# sailpi-hat.net
KiCad netlist of a schematic drawn in EAGLE
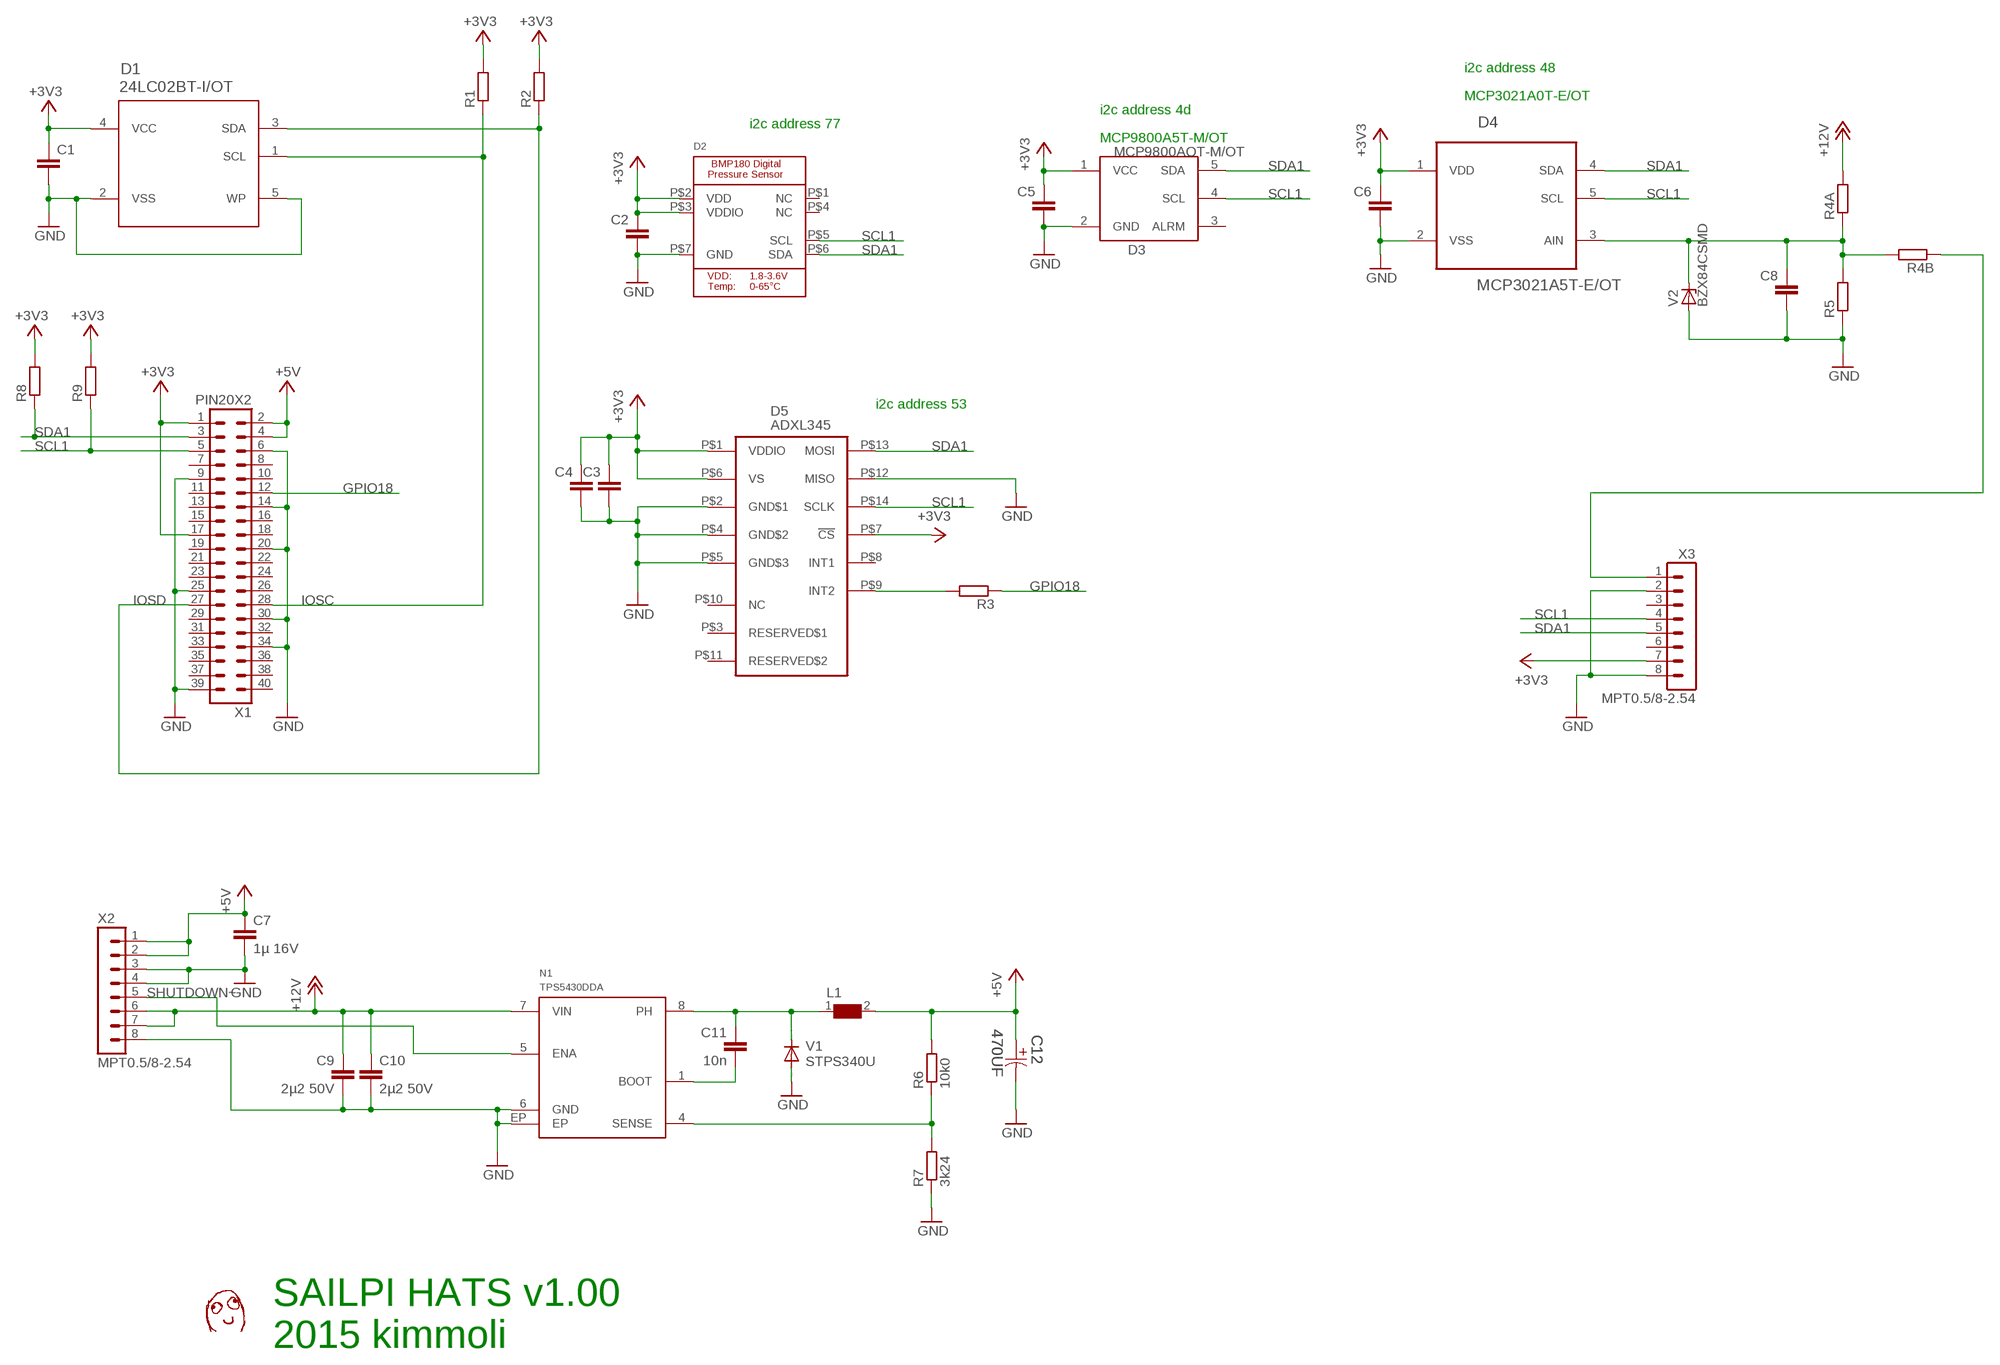
[diagram p0: schematic, sheet 1]

(export (version "E")
  (design (tool "Eeschema 10.0.6"))
  (components
    (comp (ref "C1")
      (value "CAP0603")
      (footprint "eagle-import:C0603")
      (libsource (lib "eagle-import") (part "omat_ic_2_CAP0603"))
    )
    (comp (ref "C2")
      (value "CAP0603")
      (footprint "eagle-import:C0603")
      (libsource (lib "eagle-import") (part "omat_ic_2_CAP0603"))
    )
    (comp (ref "C3")
      (value "CAP0603")
      (footprint "eagle-import:C0603")
      (libsource (lib "eagle-import") (part "omat_ic_2_CAP0603"))
    )
    (comp (ref "C4")
      (value "CAP0603")
      (footprint "eagle-import:C0603")
      (libsource (lib "eagle-import") (part "omat_ic_2_CAP0603"))
    )
    (comp (ref "C5")
      (value "CAP0603")
      (footprint "eagle-import:C0603")
      (libsource (lib "eagle-import") (part "omat_ic_2_CAP0603"))
    )
    (comp (ref "C6")
      (value "CAP0603")
      (footprint "eagle-import:C0603")
      (libsource (lib "eagle-import") (part "omat_ic_2_CAP0603"))
    )
    (comp (ref "C7")
      (value "1µ 16V")
      (footprint "eagle-import:C0805")
      (libsource (lib "eagle-import") (part "CAP0805"))
    )
    (comp (ref "C8")
      (value "CAP0603")
      (footprint "eagle-import:C0603")
      (libsource (lib "eagle-import") (part "omat_ic_2_CAP0603"))
    )
    (comp (ref "C9")
      (value "2µ2 50V")
      (footprint "eagle-import:C0805")
      (libsource (lib "eagle-import") (part "CAP0805"))
    )
    (comp (ref "C10")
      (value "2µ2 50V")
      (footprint "eagle-import:C0805")
      (libsource (lib "eagle-import") (part "CAP0805"))
    )
    (comp (ref "C11")
      (value "10n")
      (footprint "eagle-import:C0805")
      (libsource (lib "eagle-import") (part "CAP0805"))
    )
    (comp (ref "C12")
      (value "470UF")
      (footprint "eagle-import:CAPAE1350X1400N")
      (fields (field (name "MPN") "EEVFK1V471Q") (field (name "TOLERANCE") "±20 %"))
      (libsource (lib "eagle-import") (part "EEV--CASE-H13FK1V471Q"))
    )
    (comp (ref "D1")
      (value "24LC02BT-I/OT")
      (footprint "eagle-import:SOT95P280X145-5N")
      (libsource (lib "eagle-import") (part "24LC02BT-I/OT"))
    )
    (comp (ref "D2")
      (value "BMP180EXT")
      (footprint "eagle-import:BMP180_EXTENDED")
      (libsource (lib "eagle-import") (part "BMP180EXT"))
    )
    (comp (ref "D3")
      (value "MCP9800AOT-M/OT")
      (footprint "eagle-import:SOT23-5")
      (libsource (lib "eagle-import") (part "MCP9800AOT-M/OT"))
    )
    (comp (ref "D4")
      (value "MCP3021A5T-E/OT")
      (footprint "eagle-import:SOT95P270X145-5N")
      (libsource (lib "eagle-import") (part "MCP3021A5T-E/OT"))
    )
    (comp (ref "D5")
      (value "ADXL345")
      (footprint "eagle-import:LGA14")
      (libsource (lib "eagle-import") (part "ADXL345"))
    )
    (comp (ref "L1")
      (value "WE-PD-7447709220_1260/1245/1280/1210")
      (footprint "eagle-import:WE-PD_1260_1245_1280_1210")
      (fields (field (name "MPN") "7447709220"))
      (libsource (lib "eagle-import") (part "WE-PD_1260/1245/1280/1210-7447709220"))
    )
    (comp (ref "N1")
      (value "TPS5430DDA")
      (footprint "eagle-import:SOIC8-N-EP")
      (libsource (lib "eagle-import") (part "TPS5430DDA"))
    )
    (comp (ref "R1")
      (value "RES0603")
      (footprint "eagle-import:R0603")
      (libsource (lib "eagle-import") (part "omat_ic_2_RES0603"))
    )
    (comp (ref "R2")
      (value "RES0603")
      (footprint "eagle-import:R0603")
      (libsource (lib "eagle-import") (part "omat_ic_2_RES0603"))
    )
    (comp (ref "R3")
      (value "RES0603")
      (footprint "eagle-import:R0603")
      (libsource (lib "eagle-import") (part "omat_ic_2_RES0603"))
    )
    (comp (ref "R4A")
      (value "RES0603")
      (footprint "eagle-import:R0603")
      (libsource (lib "eagle-import") (part "omat_ic_2_RES0603"))
    )
    (comp (ref "R4B")
      (value "RES0603")
      (footprint "eagle-import:R0603")
      (libsource (lib "eagle-import") (part "omat_ic_2_RES0603"))
    )
    (comp (ref "R5")
      (value "RES0603")
      (footprint "eagle-import:R0603")
      (libsource (lib "eagle-import") (part "omat_ic_2_RES0603"))
    )
    (comp (ref "R6")
      (value "10k0")
      (footprint "eagle-import:R0603")
      (libsource (lib "eagle-import") (part "RES0603"))
    )
    (comp (ref "R7")
      (value "3k24")
      (footprint "eagle-import:R0603")
      (libsource (lib "eagle-import") (part "RES0603"))
    )
    (comp (ref "R8")
      (value "RES0603")
      (footprint "eagle-import:R0603")
      (libsource (lib "eagle-import") (part "omat_ic_2_RES0603"))
    )
    (comp (ref "R9")
      (value "RES0603")
      (footprint "eagle-import:R0603")
      (libsource (lib "eagle-import") (part "omat_ic_2_RES0603"))
    )
    (comp (ref "U$2")
      (value "DAFUG")
      (footprint "eagle-import:DAFUG")
      (libsource (lib "eagle-import") (part "DAFUG"))
    )
    (comp (ref "V1")
      (value "STPS340U")
      (footprint "eagle-import:SMB")
      (libsource (lib "eagle-import") (part "DIODE-SMB"))
    )
    (comp (ref "V2")
      (value "BZX84CSMD")
      (footprint "eagle-import:TO236")
      (libsource (lib "eagle-import") (part "BZX84CSMD"))
    )
    (comp (ref "X1")
      (value "PIN20X2")
      (footprint "eagle-import:PIN_20X2")
      (libsource (lib "eagle-import") (part "PIN20X2"))
    )
    (comp (ref "X2")
      (value "MPT0.5/8-2.54")
      (footprint "eagle-import:MPT0.5_8-2.54")
      (libsource (lib "eagle-import") (part "MPT0.5/8-2.54"))
    )
    (comp (ref "X3")
      (value "MPT0.5/8-2.54")
      (footprint "eagle-import:MPT0.5_8-2.54")
      (libsource (lib "eagle-import") (part "MPT0.5/8-2.54"))
    )
  )
  (nets
    (net (code "1") (name "+3V3") (class "Default")
      (node (ref "C1") (pin "1") (pinfunction "1_1") (pintype "passive"))
      (node (ref "C2") (pin "1") (pinfunction "1_1") (pintype "passive"))
      (node (ref "C3") (pin "1") (pinfunction "1_1") (pintype "passive"))
      (node (ref "C4") (pin "1") (pinfunction "1_1") (pintype "passive"))
      (node (ref "C5") (pin "1") (pinfunction "1_1") (pintype "passive"))
      (node (ref "C6") (pin "1") (pinfunction "1_1") (pintype "passive"))
      (node (ref "D1") (pin "4") (pinfunction "VCC_4") (pintype "power_in"))
      (node (ref "D2") (pin "P$2") (pinfunction "VDD_P$2") (pintype "power_in"))
      (node (ref "D2") (pin "P$3") (pinfunction "VDDIO_P$3") (pintype "power_in"))
      (node (ref "D3") (pin "1") (pinfunction "VCC_1") (pintype "bidirectional"))
      (node (ref "D4") (pin "1") (pinfunction "VDD_1") (pintype "power_in"))
      (node (ref "D5") (pin "P$1") (pinfunction "VDDIO_P$1") (pintype "power_in"))
      (node (ref "D5") (pin "P$6") (pinfunction "VS_P$6") (pintype "power_in"))
      (node (ref "D5") (pin "P$7") (pinfunction "~{CS}_P$7") (pintype "input"))
      (node (ref "R1") (pin "2") (pinfunction "2_2") (pintype "passive"))
      (node (ref "R2") (pin "2") (pinfunction "2_2") (pintype "passive"))
      (node (ref "R8") (pin "2") (pinfunction "2_2") (pintype "passive"))
      (node (ref "R9") (pin "2") (pinfunction "2_2") (pintype "passive"))
      (node (ref "X1") (pin "1") (pinfunction "1_1") (pintype "passive"))
      (node (ref "X1") (pin "17") (pinfunction "17_17") (pintype "passive"))
      (node (ref "X3") (pin "7") (pinfunction "7_7") (pintype "passive"))
    )
    (net (code "2") (name "+5V") (class "Default")
      (node (ref "C12") (pin "1") (pinfunction "1_1") (pintype "passive"))
      (node (ref "C7") (pin "1") (pinfunction "1_1") (pintype "passive"))
      (node (ref "L1") (pin "2") (pinfunction "2_2") (pintype "passive"))
      (node (ref "R6") (pin "2") (pinfunction "2_2") (pintype "passive"))
      (node (ref "X1") (pin "2") (pinfunction "2_2") (pintype "passive"))
      (node (ref "X1") (pin "4") (pinfunction "4_4") (pintype "passive"))
      (node (ref "X2") (pin "1") (pinfunction "1_1") (pintype "passive"))
      (node (ref "X2") (pin "2") (pinfunction "2_2") (pintype "passive"))
    )
    (net (code "3") (name "+12V") (class "Default")
      (node (ref "C10") (pin "1") (pinfunction "1_1") (pintype "passive"))
      (node (ref "C9") (pin "1") (pinfunction "1_1") (pintype "passive"))
      (node (ref "N1") (pin "7") (pinfunction "VIN_7") (pintype "bidirectional"))
      (node (ref "R4A") (pin "2") (pinfunction "2_2") (pintype "passive"))
      (node (ref "X2") (pin "6") (pinfunction "6_6") (pintype "passive"))
      (node (ref "X2") (pin "7") (pinfunction "7_7") (pintype "passive"))
    )
    (net (code "4") (name "/GPIO18") (class "Default")
      (node (ref "R3") (pin "1") (pinfunction "1_1") (pintype "passive"))
      (node (ref "X1") (pin "12") (pinfunction "12_12") (pintype "passive"))
    )
    (net (code "5") (name "/IOSC") (class "Default")
      (node (ref "D1") (pin "1") (pinfunction "SCL_1") (pintype "input"))
      (node (ref "R1") (pin "1") (pinfunction "1_1") (pintype "passive"))
      (node (ref "X1") (pin "28") (pinfunction "28_28") (pintype "passive"))
    )
    (net (code "6") (name "/IOSD") (class "Default")
      (node (ref "D1") (pin "3") (pinfunction "SDA_3") (pintype "bidirectional"))
      (node (ref "R2") (pin "1") (pinfunction "1_1") (pintype "passive"))
      (node (ref "X1") (pin "27") (pinfunction "27_27") (pintype "passive"))
    )
    (net (code "7") (name "/SCL1") (class "Default")
      (node (ref "D2") (pin "P$5") (pinfunction "SCL_P$5") (pintype "bidirectional"))
      (node (ref "D3") (pin "4") (pinfunction "SCL_4") (pintype "bidirectional"))
      (node (ref "D4") (pin "5") (pinfunction "SCL_5") (pintype "input"))
      (node (ref "D5") (pin "P$14") (pinfunction "SCLK_P$14") (pintype "input"))
      (node (ref "R9") (pin "1") (pinfunction "1_1") (pintype "passive"))
      (node (ref "X1") (pin "5") (pinfunction "5_5") (pintype "passive"))
      (node (ref "X3") (pin "4") (pinfunction "4_4") (pintype "passive"))
    )
    (net (code "8") (name "/SDA1") (class "Default")
      (node (ref "D2") (pin "P$6") (pinfunction "SDA_P$6") (pintype "bidirectional"))
      (node (ref "D3") (pin "5") (pinfunction "SDA_5") (pintype "bidirectional"))
      (node (ref "D4") (pin "4") (pinfunction "SDA_4") (pintype "bidirectional"))
      (node (ref "D5") (pin "P$13") (pinfunction "MOSI_P$13") (pintype "input"))
      (node (ref "R8") (pin "1") (pinfunction "1_1") (pintype "passive"))
      (node (ref "X1") (pin "3") (pinfunction "3_3") (pintype "passive"))
      (node (ref "X3") (pin "5") (pinfunction "5_5") (pintype "passive"))
    )
    (net (code "9") (name "/SHUTDOWN~{}") (class "Default")
      (node (ref "N1") (pin "5") (pinfunction "ENA_5") (pintype "bidirectional"))
      (node (ref "X2") (pin "5") (pinfunction "5_5") (pintype "passive"))
    )
    (net (code "10") (name "GND") (class "Default")
      (node (ref "C1") (pin "2") (pinfunction "2_2") (pintype "passive"))
      (node (ref "C10") (pin "2") (pinfunction "2_2") (pintype "passive"))
      (node (ref "C12") (pin "2") (pinfunction "2_2") (pintype "passive"))
      (node (ref "C2") (pin "2") (pinfunction "2_2") (pintype "passive"))
      (node (ref "C3") (pin "2") (pinfunction "2_2") (pintype "passive"))
      (node (ref "C4") (pin "2") (pinfunction "2_2") (pintype "passive"))
      (node (ref "C5") (pin "2") (pinfunction "2_2") (pintype "passive"))
      (node (ref "C6") (pin "2") (pinfunction "2_2") (pintype "passive"))
      (node (ref "C7") (pin "2") (pinfunction "2_2") (pintype "passive"))
      (node (ref "C8") (pin "2") (pinfunction "2_2") (pintype "passive"))
      (node (ref "C9") (pin "2") (pinfunction "2_2") (pintype "passive"))
      (node (ref "D1") (pin "2") (pinfunction "VSS_2") (pintype "passive"))
      (node (ref "D1") (pin "5") (pinfunction "WP_5") (pintype "input"))
      (node (ref "D2") (pin "P$7") (pinfunction "GND_P$7") (pintype "power_in"))
      (node (ref "D3") (pin "2") (pinfunction "GND_2") (pintype "bidirectional"))
      (node (ref "D4") (pin "2") (pinfunction "VSS_2") (pintype "passive"))
      (node (ref "D5") (pin "P$12") (pinfunction "MISO_P$12") (pintype "output"))
      (node (ref "D5") (pin "P$2") (pinfunction "GND$1_P$2") (pintype "power_in"))
      (node (ref "D5") (pin "P$4") (pinfunction "GND$2_P$4") (pintype "power_in"))
      (node (ref "D5") (pin "P$5") (pinfunction "GND$3_P$5") (pintype "power_in"))
      (node (ref "N1") (pin "6") (pinfunction "GND_6") (pintype "bidirectional"))
      (node (ref "N1") (pin "EP") (pinfunction "EP_EP") (pintype "bidirectional"))
      (node (ref "R5") (pin "1") (pinfunction "1_1") (pintype "passive"))
      (node (ref "R7") (pin "1") (pinfunction "1_1") (pintype "passive"))
      (node (ref "V1") (pin "A") (pinfunction "A_A") (pintype "passive"))
      (node (ref "V2") (pin "A") (pinfunction "A_A") (pintype "passive"))
      (node (ref "X1") (pin "14") (pinfunction "14_14") (pintype "passive"))
      (node (ref "X1") (pin "20") (pinfunction "20_20") (pintype "passive"))
      (node (ref "X1") (pin "25") (pinfunction "25_25") (pintype "passive"))
      (node (ref "X1") (pin "30") (pinfunction "30_30") (pintype "passive"))
      (node (ref "X1") (pin "34") (pinfunction "34_34") (pintype "passive"))
      (node (ref "X1") (pin "39") (pinfunction "39_39") (pintype "passive"))
      (node (ref "X1") (pin "6") (pinfunction "6_6") (pintype "passive"))
      (node (ref "X1") (pin "9") (pinfunction "9_9") (pintype "passive"))
      (node (ref "X2") (pin "3") (pinfunction "3_3") (pintype "passive"))
      (node (ref "X2") (pin "4") (pinfunction "4_4") (pintype "passive"))
      (node (ref "X2") (pin "8") (pinfunction "8_8") (pintype "passive"))
      (node (ref "X3") (pin "2") (pinfunction "2_2") (pintype "passive"))
      (node (ref "X3") (pin "8") (pinfunction "8_8") (pintype "passive"))
    )
    (net (code "11") (name "Net-(D4-AIN)") (class "Default")
      (node (ref "C8") (pin "1") (pinfunction "1_1") (pintype "passive"))
      (node (ref "D4") (pin "3") (pinfunction "AIN_3") (pintype "input"))
      (node (ref "R4A") (pin "1") (pinfunction "1_1") (pintype "passive"))
      (node (ref "R4B") (pin "2") (pinfunction "2_2") (pintype "passive"))
      (node (ref "R5") (pin "2") (pinfunction "2_2") (pintype "passive"))
      (node (ref "V2") (pin "C") (pinfunction "C_C") (pintype "passive"))
    )
    (net (code "12") (name "Net-(D5-INT2)") (class "Default")
      (node (ref "D5") (pin "P$9") (pinfunction "INT2_P$9") (pintype "output"))
      (node (ref "R3") (pin "2") (pinfunction "2_2") (pintype "passive"))
    )
    (net (code "13") (name "Net-(N1-BOOT)") (class "Default")
      (node (ref "C11") (pin "2") (pinfunction "2_2") (pintype "passive"))
      (node (ref "N1") (pin "1") (pinfunction "BOOT_1") (pintype "bidirectional"))
    )
    (net (code "14") (name "Net-(N1-PH)") (class "Default")
      (node (ref "C11") (pin "1") (pinfunction "1_1") (pintype "passive"))
      (node (ref "L1") (pin "1") (pinfunction "1_1") (pintype "passive"))
      (node (ref "N1") (pin "8") (pinfunction "PH_8") (pintype "bidirectional"))
      (node (ref "V1") (pin "C") (pinfunction "C_C") (pintype "passive"))
    )
    (net (code "15") (name "Net-(N1-SENSE)") (class "Default")
      (node (ref "N1") (pin "4") (pinfunction "SENSE_4") (pintype "bidirectional"))
      (node (ref "R6") (pin "1") (pinfunction "1_1") (pintype "passive"))
      (node (ref "R7") (pin "2") (pinfunction "2_2") (pintype "passive"))
    )
    (net (code "16") (name "Net-(R4B-Pad1)") (class "Default")
      (node (ref "R4B") (pin "1") (pinfunction "1_1") (pintype "passive"))
      (node (ref "X3") (pin "1") (pinfunction "1_1") (pintype "passive"))
    )
    (net (code "17") (name "unconnected-(D2-NC-PadP$1)") (class "Default")
      (node (ref "D2") (pin "P$1") (pinfunction "NC_P$1") (pintype "no_connect"))
    )
    (net (code "18") (name "unconnected-(D2-NC-PadP$4)") (class "Default")
      (node (ref "D2") (pin "P$4") (pinfunction "NC_P$4") (pintype "no_connect"))
    )
    (net (code "19") (name "unconnected-(D3-ALRM-Pad3)") (class "Default")
      (node (ref "D3") (pin "3") (pinfunction "ALRM_3") (pintype "bidirectional"))
    )
    (net (code "20") (name "unconnected-(D5-INT1-PadP$8)") (class "Default")
      (node (ref "D5") (pin "P$8") (pinfunction "INT1_P$8") (pintype "output"))
    )
    (net (code "21") (name "unconnected-(D5-NC-PadP$10)") (class "Default")
      (node (ref "D5") (pin "P$10") (pinfunction "NC_P$10") (pintype "bidirectional"))
    )
    (net (code "22") (name "unconnected-(D5-RESERVED$1-PadP$3)") (class "Default")
      (node (ref "D5") (pin "P$3") (pinfunction "RESERVED$1_P$3") (pintype "bidirectional"))
    )
    (net (code "23") (name "unconnected-(D5-RESERVED$2-PadP$11)") (class "Default")
      (node (ref "D5") (pin "P$11") (pinfunction "RESERVED$2_P$11") (pintype "bidirectional"))
    )
    (net (code "24") (name "unconnected-(X1-Pad7)") (class "Default")
      (node (ref "X1") (pin "7") (pinfunction "7_7") (pintype "passive"))
    )
    (net (code "25") (name "unconnected-(X1-Pad8)") (class "Default")
      (node (ref "X1") (pin "8") (pinfunction "8_8") (pintype "passive"))
    )
    (net (code "26") (name "unconnected-(X1-Pad10)") (class "Default")
      (node (ref "X1") (pin "10") (pinfunction "10_10") (pintype "passive"))
    )
    (net (code "27") (name "unconnected-(X1-Pad11)") (class "Default")
      (node (ref "X1") (pin "11") (pinfunction "11_11") (pintype "passive"))
    )
    (net (code "28") (name "unconnected-(X1-Pad13)") (class "Default")
      (node (ref "X1") (pin "13") (pinfunction "13_13") (pintype "passive"))
    )
    (net (code "29") (name "unconnected-(X1-Pad15)") (class "Default")
      (node (ref "X1") (pin "15") (pinfunction "15_15") (pintype "passive"))
    )
    (net (code "30") (name "unconnected-(X1-Pad16)") (class "Default")
      (node (ref "X1") (pin "16") (pinfunction "16_16") (pintype "passive"))
    )
    (net (code "31") (name "unconnected-(X1-Pad18)") (class "Default")
      (node (ref "X1") (pin "18") (pinfunction "18_18") (pintype "passive"))
    )
    (net (code "32") (name "unconnected-(X1-Pad19)") (class "Default")
      (node (ref "X1") (pin "19") (pinfunction "19_19") (pintype "passive"))
    )
    (net (code "33") (name "unconnected-(X1-Pad21)") (class "Default")
      (node (ref "X1") (pin "21") (pinfunction "21_21") (pintype "passive"))
    )
    (net (code "34") (name "unconnected-(X1-Pad22)") (class "Default")
      (node (ref "X1") (pin "22") (pinfunction "22_22") (pintype "passive"))
    )
    (net (code "35") (name "unconnected-(X1-Pad23)") (class "Default")
      (node (ref "X1") (pin "23") (pinfunction "23_23") (pintype "passive"))
    )
    (net (code "36") (name "unconnected-(X1-Pad24)") (class "Default")
      (node (ref "X1") (pin "24") (pinfunction "24_24") (pintype "passive"))
    )
    (net (code "37") (name "unconnected-(X1-Pad26)") (class "Default")
      (node (ref "X1") (pin "26") (pinfunction "26_26") (pintype "passive"))
    )
    (net (code "38") (name "unconnected-(X1-Pad29)") (class "Default")
      (node (ref "X1") (pin "29") (pinfunction "29_29") (pintype "passive"))
    )
    (net (code "39") (name "unconnected-(X1-Pad31)") (class "Default")
      (node (ref "X1") (pin "31") (pinfunction "31_31") (pintype "passive"))
    )
    (net (code "40") (name "unconnected-(X1-Pad32)") (class "Default")
      (node (ref "X1") (pin "32") (pinfunction "32_32") (pintype "passive"))
    )
    (net (code "41") (name "unconnected-(X1-Pad33)") (class "Default")
      (node (ref "X1") (pin "33") (pinfunction "33_33") (pintype "passive"))
    )
    (net (code "42") (name "unconnected-(X1-Pad35)") (class "Default")
      (node (ref "X1") (pin "35") (pinfunction "35_35") (pintype "passive"))
    )
    (net (code "43") (name "unconnected-(X1-Pad36)") (class "Default")
      (node (ref "X1") (pin "36") (pinfunction "36_36") (pintype "passive"))
    )
    (net (code "44") (name "unconnected-(X1-Pad37)") (class "Default")
      (node (ref "X1") (pin "37") (pinfunction "37_37") (pintype "passive"))
    )
    (net (code "45") (name "unconnected-(X1-Pad38)") (class "Default")
      (node (ref "X1") (pin "38") (pinfunction "38_38") (pintype "passive"))
    )
    (net (code "46") (name "unconnected-(X1-Pad40)") (class "Default")
      (node (ref "X1") (pin "40") (pinfunction "40_40") (pintype "passive"))
    )
    (net (code "47") (name "unconnected-(X3-Pad3)") (class "Default")
      (node (ref "X3") (pin "3") (pinfunction "3_3") (pintype "passive"))
    )
    (net (code "48") (name "unconnected-(X3-Pad6)") (class "Default")
      (node (ref "X3") (pin "6") (pinfunction "6_6") (pintype "passive"))
    )
  )
)
